# Tps7A47_Tps7A33.net
KiCad netlist of a schematic drawn in EasyEDA Pro
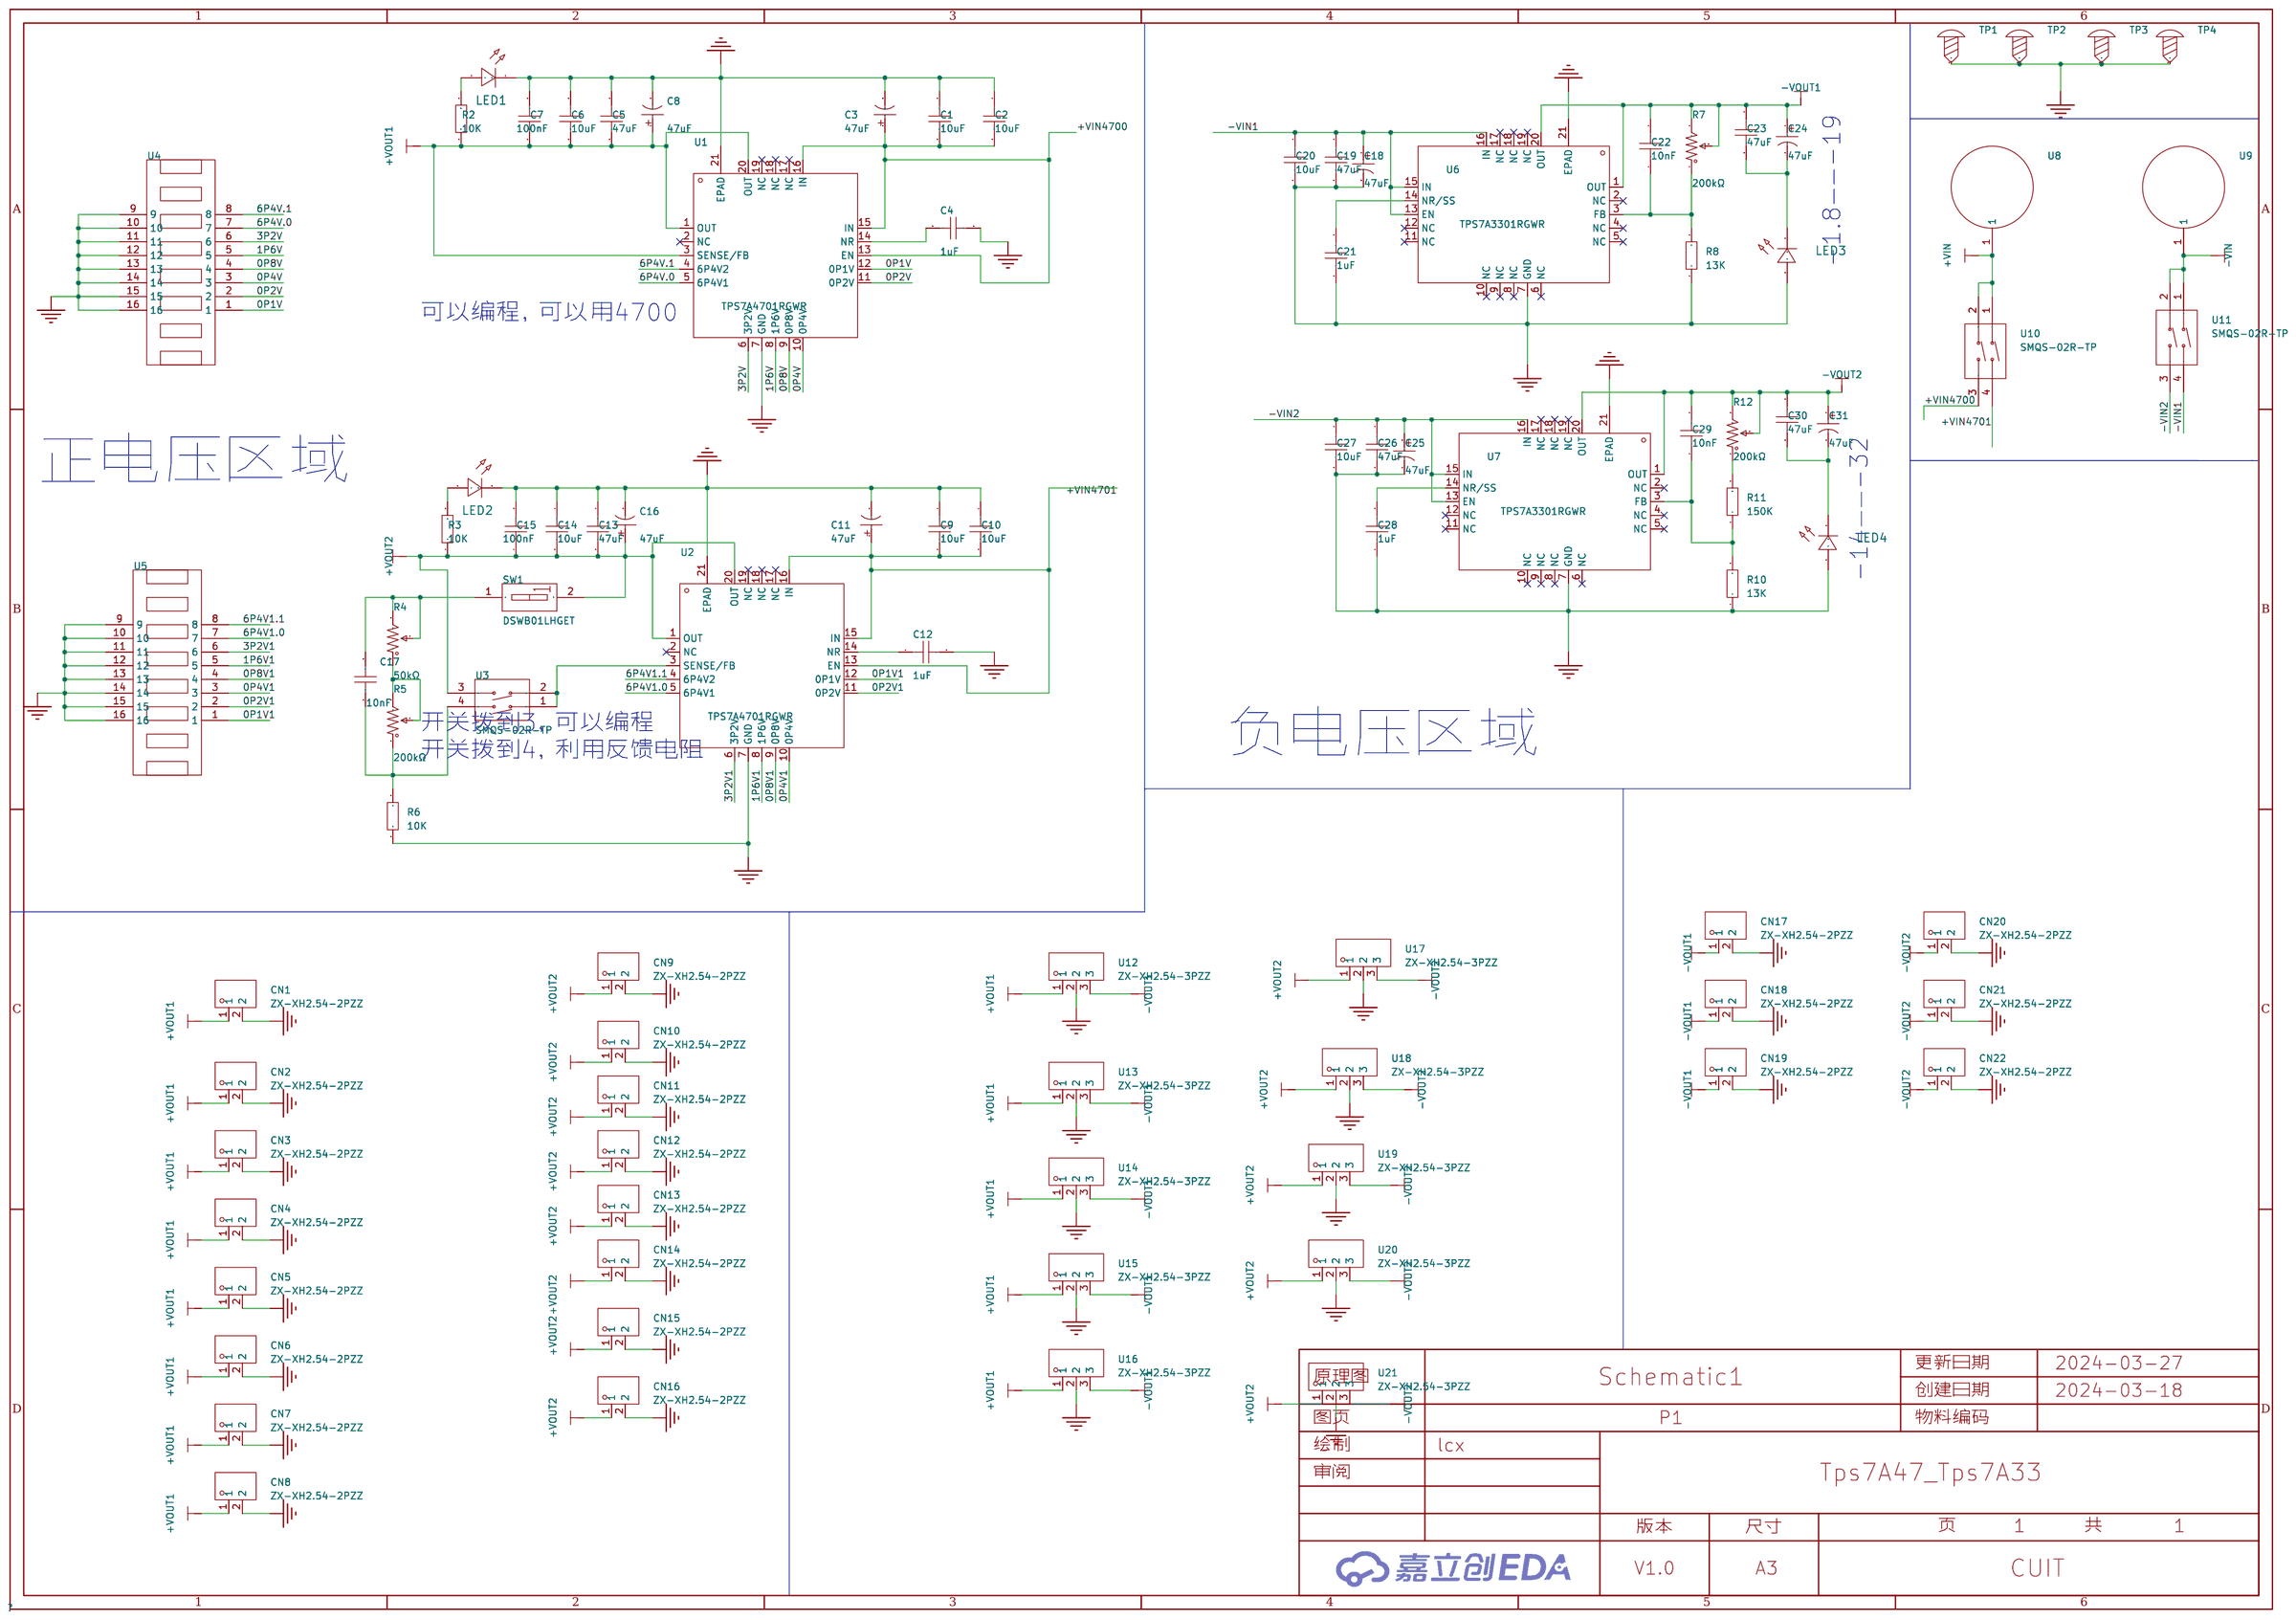
[diagram p0: schematic sheet]

(export (version "E")
  (design (tool "Eeschema 10.0.6"))
  (components
    (comp (ref "C1")
      (value "10uF")
      (footprint "easyedapro:C1206")
      (libsource (lib "easyedapro") (part "CapAcitance"))
    )
    (comp (ref "C2")
      (value "10uF")
      (footprint "easyedapro:C1206")
      (libsource (lib "easyedapro") (part "CapAcitance"))
    )
    (comp (ref "C3")
      (value "47uF")
      (footprint "easyedapro:CAP-SMD_BD6.3-L6.6-W6.6-LS7.6-FD")
      (description "容值:47uF;精度:±20%;额定电压:50V;纹波电流:66mA@120Hz;等效串联电阻:-;")
      (fields (field (name "Manufacturer Part") "RVT1H470M0607") (field (name "Manufacturer") "ROQANG(容强)"))
      (libsource (lib "easyedapro") (part "RVT1H470M0607"))
    )
    (comp (ref "C4")
      (value "1uF")
      (footprint "easyedapro:C1206")
      (libsource (lib "easyedapro") (part "CapAcitance"))
    )
    (comp (ref "C5")
      (value "47uF")
      (footprint "easyedapro:C1206")
      (libsource (lib "easyedapro") (part "CapAcitance"))
    )
    (comp (ref "C6")
      (value "10uF")
      (footprint "easyedapro:C1206")
      (libsource (lib "easyedapro") (part "CapAcitance"))
    )
    (comp (ref "C7")
      (value "100nF")
      (footprint "easyedapro:C1206")
      (libsource (lib "easyedapro") (part "CapAcitance"))
    )
    (comp (ref "C8")
      (value "47uF")
      (footprint "easyedapro:CAP-SMD_BD6.3-L6.6-W6.6-LS7.6-FD")
      (description "容值:47uF;精度:±20%;额定电压:50V;纹波电流:66mA@120Hz;等效串联电阻:-;")
      (fields (field (name "Manufacturer Part") "RVT1H470M0607") (field (name "Manufacturer") "ROQANG(容强)"))
      (libsource (lib "easyedapro") (part "RVT1H470M0607"))
    )
    (comp (ref "C9")
      (value "10uF")
      (footprint "easyedapro:C1206")
      (libsource (lib "easyedapro") (part "CapAcitance"))
    )
    (comp (ref "C10")
      (value "10uF")
      (footprint "easyedapro:C1206")
      (libsource (lib "easyedapro") (part "CapAcitance"))
    )
    (comp (ref "C11")
      (value "47uF")
      (footprint "easyedapro:CAP-SMD_BD6.3-L6.6-W6.6-LS7.6-FD")
      (description "容值:47uF;精度:±20%;额定电压:50V;纹波电流:66mA@120Hz;等效串联电阻:-;")
      (fields (field (name "Manufacturer Part") "RVT1H470M0607") (field (name "Manufacturer") "ROQANG(容强)"))
      (libsource (lib "easyedapro") (part "RVT1H470M0607"))
    )
    (comp (ref "C12")
      (value "1uF")
      (footprint "easyedapro:C1206")
      (libsource (lib "easyedapro") (part "CapAcitance"))
    )
    (comp (ref "C13")
      (value "47uF")
      (footprint "easyedapro:C1206")
      (libsource (lib "easyedapro") (part "CapAcitance"))
    )
    (comp (ref "C14")
      (value "10uF")
      (footprint "easyedapro:C1206")
      (libsource (lib "easyedapro") (part "CapAcitance"))
    )
    (comp (ref "C15")
      (value "100nF")
      (footprint "easyedapro:C1206")
      (libsource (lib "easyedapro") (part "CapAcitance"))
    )
    (comp (ref "C16")
      (value "47uF")
      (footprint "easyedapro:CAP-SMD_BD6.3-L6.6-W6.6-LS7.6-FD")
      (description "容值:47uF;精度:±20%;额定电压:50V;纹波电流:66mA@120Hz;等效串联电阻:-;")
      (fields (field (name "Manufacturer Part") "RVT1H470M0607") (field (name "Manufacturer") "ROQANG(容强)"))
      (libsource (lib "easyedapro") (part "RVT1H470M0607"))
    )
    (comp (ref "C17")
      (value "10nF")
      (footprint "easyedapro:C1206")
      (libsource (lib "easyedapro") (part "CapAcitance"))
    )
    (comp (ref "C18")
      (value "47uF")
      (footprint "easyedapro:CAP-SMD_BD6.3-L6.6-W6.6-LS7.6-FD")
      (description "容值:47uF;精度:±20%;额定电压:50V;纹波电流:66mA@120Hz;等效串联电阻:-;")
      (fields (field (name "Manufacturer Part") "RVT1H470M0607") (field (name "Manufacturer") "ROQANG(容强)"))
      (libsource (lib "easyedapro") (part "RVT1H470M0607"))
    )
    (comp (ref "C19")
      (value "47uF")
      (footprint "easyedapro:C1206")
      (libsource (lib "easyedapro") (part "CapAcitance"))
    )
    (comp (ref "C20")
      (value "10uF")
      (footprint "easyedapro:C1206")
      (libsource (lib "easyedapro") (part "CapAcitance"))
    )
    (comp (ref "C21")
      (value "1uF")
      (footprint "easyedapro:C1206")
      (libsource (lib "easyedapro") (part "CapAcitance"))
    )
    (comp (ref "C22")
      (value "10nF")
      (footprint "easyedapro:C1206")
      (libsource (lib "easyedapro") (part "CapAcitance"))
    )
    (comp (ref "C23")
      (value "47uF")
      (footprint "easyedapro:C1206")
      (libsource (lib "easyedapro") (part "CapAcitance"))
    )
    (comp (ref "C24")
      (value "47uF")
      (footprint "easyedapro:CAP-SMD_BD6.3-L6.6-W6.6-LS7.6-FD")
      (description "容值:47uF;精度:±20%;额定电压:50V;纹波电流:66mA@120Hz;等效串联电阻:-;")
      (fields (field (name "Manufacturer Part") "RVT1H470M0607") (field (name "Manufacturer") "ROQANG(容强)"))
      (libsource (lib "easyedapro") (part "RVT1H470M0607"))
    )
    (comp (ref "C25")
      (value "47uF")
      (footprint "easyedapro:CAP-SMD_BD6.3-L6.6-W6.6-LS7.6-FD")
      (description "容值:47uF;精度:±20%;额定电压:50V;纹波电流:66mA@120Hz;等效串联电阻:-;")
      (fields (field (name "Manufacturer Part") "RVT1H470M0607") (field (name "Manufacturer") "ROQANG(容强)"))
      (libsource (lib "easyedapro") (part "RVT1H470M0607"))
    )
    (comp (ref "C26")
      (value "47uF")
      (footprint "easyedapro:C1206")
      (libsource (lib "easyedapro") (part "CapAcitance"))
    )
    (comp (ref "C27")
      (value "10uF")
      (footprint "easyedapro:C1206")
      (libsource (lib "easyedapro") (part "CapAcitance"))
    )
    (comp (ref "C28")
      (value "1uF")
      (footprint "easyedapro:C1206")
      (libsource (lib "easyedapro") (part "CapAcitance"))
    )
    (comp (ref "C29")
      (value "10nF")
      (footprint "easyedapro:C1206")
      (libsource (lib "easyedapro") (part "CapAcitance"))
    )
    (comp (ref "C30")
      (value "47uF")
      (footprint "easyedapro:C1206")
      (libsource (lib "easyedapro") (part "CapAcitance"))
    )
    (comp (ref "C31")
      (value "47uF")
      (footprint "easyedapro:CAP-SMD_BD6.3-L6.6-W6.6-LS7.6-FD")
      (description "容值:47uF;精度:±20%;额定电压:50V;纹波电流:66mA@120Hz;等效串联电阻:-;")
      (fields (field (name "Manufacturer Part") "RVT1H470M0607") (field (name "Manufacturer") "ROQANG(容强)"))
      (libsource (lib "easyedapro") (part "RVT1H470M0607"))
    )
    (comp (ref "CN1")
      (value "ZX-XH2.54-2PZZ")
      (footprint "easyedapro:CONN-TH_2P-P2.50_HX25003-2A")
      (fields (field (name "Manufacturer") "Megastar(兆星)"))
      (libsource (lib "easyedapro") (part "ZX-XH2.54-2PZZ"))
    )
    (comp (ref "CN2")
      (value "ZX-XH2.54-2PZZ")
      (footprint "easyedapro:CONN-TH_2P-P2.50_HX25003-2A")
      (fields (field (name "Manufacturer") "Megastar(兆星)"))
      (libsource (lib "easyedapro") (part "ZX-XH2.54-2PZZ"))
    )
    (comp (ref "CN3")
      (value "ZX-XH2.54-2PZZ")
      (footprint "easyedapro:CONN-TH_2P-P2.50_HX25003-2A")
      (fields (field (name "Manufacturer") "Megastar(兆星)"))
      (libsource (lib "easyedapro") (part "ZX-XH2.54-2PZZ"))
    )
    (comp (ref "CN4")
      (value "ZX-XH2.54-2PZZ")
      (footprint "easyedapro:CONN-TH_2P-P2.50_HX25003-2A")
      (fields (field (name "Manufacturer") "Megastar(兆星)"))
      (libsource (lib "easyedapro") (part "ZX-XH2.54-2PZZ"))
    )
    (comp (ref "CN5")
      (value "ZX-XH2.54-2PZZ")
      (footprint "easyedapro:CONN-TH_2P-P2.50_HX25003-2A")
      (fields (field (name "Manufacturer") "Megastar(兆星)"))
      (libsource (lib "easyedapro") (part "ZX-XH2.54-2PZZ"))
    )
    (comp (ref "CN6")
      (value "ZX-XH2.54-2PZZ")
      (footprint "easyedapro:CONN-TH_2P-P2.50_HX25003-2A")
      (fields (field (name "Manufacturer") "Megastar(兆星)"))
      (libsource (lib "easyedapro") (part "ZX-XH2.54-2PZZ"))
    )
    (comp (ref "CN7")
      (value "ZX-XH2.54-2PZZ")
      (footprint "easyedapro:CONN-TH_2P-P2.50_HX25003-2A")
      (fields (field (name "Manufacturer") "Megastar(兆星)"))
      (libsource (lib "easyedapro") (part "ZX-XH2.54-2PZZ"))
    )
    (comp (ref "CN8")
      (value "ZX-XH2.54-2PZZ")
      (footprint "easyedapro:CONN-TH_2P-P2.50_HX25003-2A")
      (fields (field (name "Manufacturer") "Megastar(兆星)"))
      (libsource (lib "easyedapro") (part "ZX-XH2.54-2PZZ"))
    )
    (comp (ref "CN9")
      (value "ZX-XH2.54-2PZZ")
      (footprint "easyedapro:CONN-TH_2P-P2.50_HX25003-2A")
      (fields (field (name "Manufacturer") "Megastar(兆星)"))
      (libsource (lib "easyedapro") (part "ZX-XH2.54-2PZZ"))
    )
    (comp (ref "CN10")
      (value "ZX-XH2.54-2PZZ")
      (footprint "easyedapro:CONN-TH_2P-P2.50_HX25003-2A")
      (fields (field (name "Manufacturer") "Megastar(兆星)"))
      (libsource (lib "easyedapro") (part "ZX-XH2.54-2PZZ"))
    )
    (comp (ref "CN11")
      (value "ZX-XH2.54-2PZZ")
      (footprint "easyedapro:CONN-TH_2P-P2.50_HX25003-2A")
      (fields (field (name "Manufacturer") "Megastar(兆星)"))
      (libsource (lib "easyedapro") (part "ZX-XH2.54-2PZZ"))
    )
    (comp (ref "CN12")
      (value "ZX-XH2.54-2PZZ")
      (footprint "easyedapro:CONN-TH_2P-P2.50_HX25003-2A")
      (fields (field (name "Manufacturer") "Megastar(兆星)"))
      (libsource (lib "easyedapro") (part "ZX-XH2.54-2PZZ"))
    )
    (comp (ref "CN13")
      (value "ZX-XH2.54-2PZZ")
      (footprint "easyedapro:CONN-TH_2P-P2.50_HX25003-2A")
      (fields (field (name "Manufacturer") "Megastar(兆星)"))
      (libsource (lib "easyedapro") (part "ZX-XH2.54-2PZZ"))
    )
    (comp (ref "CN14")
      (value "ZX-XH2.54-2PZZ")
      (footprint "easyedapro:CONN-TH_2P-P2.50_HX25003-2A")
      (fields (field (name "Manufacturer") "Megastar(兆星)"))
      (libsource (lib "easyedapro") (part "ZX-XH2.54-2PZZ"))
    )
    (comp (ref "CN15")
      (value "ZX-XH2.54-2PZZ")
      (footprint "easyedapro:CONN-TH_2P-P2.50_HX25003-2A")
      (fields (field (name "Manufacturer") "Megastar(兆星)"))
      (libsource (lib "easyedapro") (part "ZX-XH2.54-2PZZ"))
    )
    (comp (ref "CN16")
      (value "ZX-XH2.54-2PZZ")
      (footprint "easyedapro:CONN-TH_2P-P2.50_HX25003-2A")
      (fields (field (name "Manufacturer") "Megastar(兆星)"))
      (libsource (lib "easyedapro") (part "ZX-XH2.54-2PZZ"))
    )
    (comp (ref "CN17")
      (value "ZX-XH2.54-2PZZ")
      (footprint "easyedapro:CONN-TH_2P-P2.50_HX25003-2A")
      (fields (field (name "Manufacturer") "Megastar(兆星)"))
      (libsource (lib "easyedapro") (part "ZX-XH2.54-2PZZ"))
    )
    (comp (ref "CN18")
      (value "ZX-XH2.54-2PZZ")
      (footprint "easyedapro:CONN-TH_2P-P2.50_HX25003-2A")
      (fields (field (name "Manufacturer") "Megastar(兆星)"))
      (libsource (lib "easyedapro") (part "ZX-XH2.54-2PZZ"))
    )
    (comp (ref "CN19")
      (value "ZX-XH2.54-2PZZ")
      (footprint "easyedapro:CONN-TH_2P-P2.50_HX25003-2A")
      (fields (field (name "Manufacturer") "Megastar(兆星)"))
      (libsource (lib "easyedapro") (part "ZX-XH2.54-2PZZ"))
    )
    (comp (ref "CN20")
      (value "ZX-XH2.54-2PZZ")
      (footprint "easyedapro:CONN-TH_2P-P2.50_HX25003-2A")
      (fields (field (name "Manufacturer") "Megastar(兆星)"))
      (libsource (lib "easyedapro") (part "ZX-XH2.54-2PZZ"))
    )
    (comp (ref "CN21")
      (value "ZX-XH2.54-2PZZ")
      (footprint "easyedapro:CONN-TH_2P-P2.50_HX25003-2A")
      (fields (field (name "Manufacturer") "Megastar(兆星)"))
      (libsource (lib "easyedapro") (part "ZX-XH2.54-2PZZ"))
    )
    (comp (ref "CN22")
      (value "ZX-XH2.54-2PZZ")
      (footprint "easyedapro:CONN-TH_2P-P2.50_HX25003-2A")
      (fields (field (name "Manufacturer") "Megastar(兆星)"))
      (libsource (lib "easyedapro") (part "ZX-XH2.54-2PZZ"))
    )
    (comp (ref "LED1")
      (value "~")
      (footprint "easyedapro:LED_0805")
      (libsource (lib "easyedapro") (part "LED_R"))
    )
    (comp (ref "LED2")
      (value "~")
      (footprint "easyedapro:LED_0805")
      (libsource (lib "easyedapro") (part "LED_R"))
    )
    (comp (ref "LED3")
      (value "~")
      (footprint "easyedapro:LED_0805")
      (libsource (lib "easyedapro") (part "LED_R"))
    )
    (comp (ref "LED4")
      (value "~")
      (footprint "easyedapro:LED_0805")
      (libsource (lib "easyedapro") (part "LED_R"))
    )
    (comp (ref "R2") (value "10K") (footprint "easyedapro:R0805") (libsource (lib "easyedapro") (part "电阻")))
    (comp (ref "R3") (value "10K") (footprint "easyedapro:R0805") (libsource (lib "easyedapro") (part "电阻")))
    (comp (ref "R4")
      (value "50kΩ")
      (footprint "easyedapro:RES-ADJ-TH_3P-L10.0-W10.0-P2.50-L")
      (description "阻值:10kΩ;精度:±10%;")
      (fields (field (name "Manufacturer Part") "3296W-1-103") (field (name "Manufacturer") "BOCHEN(博晨)"))
      (libsource (lib "easyedapro") (part "3296W-1-103"))
    )
    (comp (ref "R5")
      (value "200kΩ")
      (footprint "easyedapro:RES-ADJ-TH_3P-L10.0-W10.0-P2.50-L")
      (description "阻值:10kΩ;精度:±10%;")
      (fields (field (name "Manufacturer Part") "3296W-1-103") (field (name "Manufacturer") "BOCHEN(博晨)"))
      (libsource (lib "easyedapro") (part "3296W-1-103"))
    )
    (comp (ref "R6") (value "10K") (footprint "easyedapro:R0805") (libsource (lib "easyedapro") (part "电阻")))
    (comp (ref "R7")
      (value "200kΩ")
      (footprint "easyedapro:RES-ADJ-TH_3P-L10.0-W10.0-P2.50-L")
      (description "阻值:10kΩ;精度:±10%;")
      (fields (field (name "Manufacturer Part") "3296W-1-103") (field (name "Manufacturer") "BOCHEN(博晨)"))
      (libsource (lib "easyedapro") (part "3296W-1-103"))
    )
    (comp (ref "R8") (value "13K") (footprint "easyedapro:R0805") (libsource (lib "easyedapro") (part "电阻")))
    (comp (ref "R10") (value "13K") (footprint "easyedapro:R0805") (libsource (lib "easyedapro") (part "电阻")))
    (comp (ref "R11")
      (value "150K")
      (footprint "easyedapro:R0805")
      (libsource (lib "easyedapro") (part "电阻"))
    )
    (comp (ref "R12")
      (value "200kΩ")
      (footprint "easyedapro:RES-ADJ-TH_3P-L10.0-W10.0-P2.50-L")
      (description "阻值:10kΩ;精度:±10%;")
      (fields (field (name "Manufacturer Part") "3296W-1-103") (field (name "Manufacturer") "BOCHEN(博晨)"))
      (libsource (lib "easyedapro") (part "3296W-1-103"))
    )
    (comp (ref "SW1")
      (value "DSWB01LHGET")
      (footprint "easyedapro:SW-TH_DSWB01LHGET")
      (description "类型:平拨,凸起式;电路结构:单刀单掷;开关位数:1位;使用寿命:-;颜色:红色;")
      (fields (field (name "Manufacturer") "YE"))
      (libsource (lib "easyedapro") (part "DSWB01LHGET"))
    )
    (comp (ref "TP1") (value "~") (footprint "easyedapro:M2螺丝") (libsource (lib "easyedapro") (part "螺丝孔")))
    (comp (ref "TP2") (value "~") (footprint "easyedapro:M2螺丝") (libsource (lib "easyedapro") (part "螺丝孔")))
    (comp (ref "TP3") (value "~") (footprint "easyedapro:M2螺丝") (libsource (lib "easyedapro") (part "螺丝孔")))
    (comp (ref "TP4") (value "~") (footprint "easyedapro:M2螺丝") (libsource (lib "easyedapro") (part "螺丝孔")))
    (comp (ref "U1")
      (value "TPS7A4701RGWR")
      (footprint "easyedapro:VQFN-20_L5.0-W5.0-P0.65-TL-EP")
      (description "输出类型:可调;最大输入电压:35V;输出电压:1.4V~34V;最大输出电流:1A;电源纹波抑制比(PSRR):78dB@(1kHz);输出极性:正极;")
      (fields (field (name "Manufacturer") "TI(德州仪器)"))
      (libsource (lib "easyedapro") (part "TPS7A4701RGWR"))
    )
    (comp (ref "U2")
      (value "TPS7A4701RGWR")
      (footprint "easyedapro:VQFN-20_L5.0-W5.0-P0.65-TL-EP")
      (description "输出类型:可调;最大输入电压:35V;输出电压:1.4V~34V;最大输出电流:1A;电源纹波抑制比(PSRR):78dB@(1kHz);输出极性:正极;")
      (fields (field (name "Manufacturer") "TI(德州仪器)"))
      (libsource (lib "easyedapro") (part "TPS7A4701RGWR"))
    )
    (comp (ref "U3")
      (value "SMQS-02R-TP")
      (footprint "easyedapro:SW-TH_4P-L9.9-W6.8-P7.62-BL")
      (description "类型:平拨,凸起式;电路结构:-;开关位数:2位;额定电流:-;额定电压:-;使用寿命:5千次;颜色:红色;")
      (fields (field (name "Manufacturer") "SM Switch"))
      (libsource (lib "easyedapro") (part "SMQS-02R-TP"))
    )
    (comp (ref "U4") (value "~") (footprint "easyedapro:DIP16") (libsource (lib "easyedapro") (part "DS8RT")))
    (comp (ref "U5") (value "~") (footprint "easyedapro:DIP16") (libsource (lib "easyedapro") (part "DS8RT")))
    (comp (ref "U6")
      (value "TPS7A3301RGWR")
      (footprint "easyedapro:VQFN-20_L5.0-W5.0-P0.65-TL-EP")
      (description "输出类型:可调;最大输入电压:36V;输出电压:1.18V~33V;最大输出电流:1A;电源纹波抑制比(PSRR):72dB@(10kHz);输出极性:负极;")
      (fields (field (name "Manufacturer") "TI(德州仪器)"))
      (libsource (lib "easyedapro") (part "TPS7A3301RGWR"))
    )
    (comp (ref "U7")
      (value "TPS7A3301RGWR")
      (footprint "easyedapro:VQFN-20_L5.0-W5.0-P0.65-TL-EP")
      (description "输出类型:可调;最大输入电压:36V;输出电压:1.18V~33V;最大输出电流:1A;电源纹波抑制比(PSRR):72dB@(10kHz);输出极性:负极;")
      (fields (field (name "Manufacturer") "TI(德州仪器)"))
      (libsource (lib "easyedapro") (part "TPS7A3301RGWR"))
    )
    (comp (ref "U8")
      (value "~")
      (footprint "easyedapro:插座")
      (libsource (lib "easyedapro") (part "4mmbananaheader"))
    )
    (comp (ref "U9")
      (value "~")
      (footprint "easyedapro:插座")
      (libsource (lib "easyedapro") (part "4mmbananaheader"))
    )
    (comp (ref "U10")
      (value "SMQS-02R-TP")
      (footprint "easyedapro:SW-TH_4P-L9.9-W6.8-P7.62-BL")
      (description "类型:平拨,凸起式;电路结构:-;开关位数:2位;额定电流:-;额定电压:-;使用寿命:5千次;颜色:红色;")
      (fields (field (name "Manufacturer") "SM Switch"))
      (libsource (lib "easyedapro") (part "SMQS-02R-TP"))
    )
    (comp (ref "U11")
      (value "SMQS-02R-TP")
      (footprint "easyedapro:SW-TH_4P-L9.9-W6.8-P7.62-BL")
      (description "类型:平拨,凸起式;电路结构:-;开关位数:2位;额定电流:-;额定电压:-;使用寿命:5千次;颜色:红色;")
      (fields (field (name "Manufacturer") "SM Switch"))
      (libsource (lib "easyedapro") (part "SMQS-02R-TP"))
    )
    (comp (ref "U12")
      (value "ZX-XH2.54-3PZZ")
      (footprint "easyedapro:CONN-TH_3P-P2.54_2501S-3P")
      (fields (field (name "Manufacturer") "Megastar(兆星)"))
      (libsource (lib "easyedapro") (part "ZX-XH2.54-3PZZ"))
    )
    (comp (ref "U13")
      (value "ZX-XH2.54-3PZZ")
      (footprint "easyedapro:CONN-TH_3P-P2.54_2501S-3P")
      (fields (field (name "Manufacturer") "Megastar(兆星)"))
      (libsource (lib "easyedapro") (part "ZX-XH2.54-3PZZ"))
    )
    (comp (ref "U14")
      (value "ZX-XH2.54-3PZZ")
      (footprint "easyedapro:CONN-TH_3P-P2.54_2501S-3P")
      (fields (field (name "Manufacturer") "Megastar(兆星)"))
      (libsource (lib "easyedapro") (part "ZX-XH2.54-3PZZ"))
    )
    (comp (ref "U15")
      (value "ZX-XH2.54-3PZZ")
      (footprint "easyedapro:CONN-TH_3P-P2.54_2501S-3P")
      (fields (field (name "Manufacturer") "Megastar(兆星)"))
      (libsource (lib "easyedapro") (part "ZX-XH2.54-3PZZ"))
    )
    (comp (ref "U16")
      (value "ZX-XH2.54-3PZZ")
      (footprint "easyedapro:CONN-TH_3P-P2.54_2501S-3P")
      (fields (field (name "Manufacturer") "Megastar(兆星)"))
      (libsource (lib "easyedapro") (part "ZX-XH2.54-3PZZ"))
    )
    (comp (ref "U17")
      (value "ZX-XH2.54-3PZZ")
      (footprint "easyedapro:CONN-TH_3P-P2.54_2501S-3P")
      (fields (field (name "Manufacturer") "Megastar(兆星)"))
      (libsource (lib "easyedapro") (part "ZX-XH2.54-3PZZ"))
    )
    (comp (ref "U18")
      (value "ZX-XH2.54-3PZZ")
      (footprint "easyedapro:CONN-TH_3P-P2.54_2501S-3P")
      (fields (field (name "Manufacturer") "Megastar(兆星)"))
      (libsource (lib "easyedapro") (part "ZX-XH2.54-3PZZ"))
    )
    (comp (ref "U19")
      (value "ZX-XH2.54-3PZZ")
      (footprint "easyedapro:CONN-TH_3P-P2.54_2501S-3P")
      (fields (field (name "Manufacturer") "Megastar(兆星)"))
      (libsource (lib "easyedapro") (part "ZX-XH2.54-3PZZ"))
    )
    (comp (ref "U20")
      (value "ZX-XH2.54-3PZZ")
      (footprint "easyedapro:CONN-TH_3P-P2.54_2501S-3P")
      (fields (field (name "Manufacturer") "Megastar(兆星)"))
      (libsource (lib "easyedapro") (part "ZX-XH2.54-3PZZ"))
    )
    (comp (ref "U21")
      (value "ZX-XH2.54-3PZZ")
      (footprint "easyedapro:CONN-TH_3P-P2.54_2501S-3P")
      (fields (field (name "Manufacturer") "Megastar(兆星)"))
      (libsource (lib "easyedapro") (part "ZX-XH2.54-3PZZ"))
    )
  )
  (nets
    (net (code "1") (name "+VIN") (class "Default")
      (node (ref "U10") (pin "1") (pinfunction "1_1") (pintype "unspecified"))
      (node (ref "U10") (pin "2") (pinfunction "2_2") (pintype "unspecified"))
      (node (ref "U8") (pin "1") (pinfunction "1_1") (pintype "input"))
    )
    (net (code "2") (name "+VOUT1") (class "Default")
      (node (ref "C5") (pin "2") (pinfunction "2_2") (pintype "input"))
      (node (ref "C6") (pin "2") (pinfunction "2_2") (pintype "input"))
      (node (ref "C7") (pin "1") (pinfunction "1_1") (pintype "input"))
      (node (ref "C8") (pin "1") (pinfunction "1_1") (pintype "input"))
      (node (ref "CN1") (pin "1") (pinfunction "1_1") (pintype "unspecified"))
      (node (ref "CN2") (pin "1") (pinfunction "1_1") (pintype "unspecified"))
      (node (ref "CN3") (pin "1") (pinfunction "1_1") (pintype "unspecified"))
      (node (ref "CN4") (pin "1") (pinfunction "1_1") (pintype "unspecified"))
      (node (ref "CN5") (pin "1") (pinfunction "1_1") (pintype "unspecified"))
      (node (ref "CN6") (pin "1") (pinfunction "1_1") (pintype "unspecified"))
      (node (ref "CN7") (pin "1") (pinfunction "1_1") (pintype "unspecified"))
      (node (ref "CN8") (pin "1") (pinfunction "1_1") (pintype "unspecified"))
      (node (ref "R2") (pin "1") (pinfunction "1_1") (pintype "input"))
      (node (ref "U1") (pin "1") (pinfunction "OUT_1") (pintype "unspecified"))
      (node (ref "U1") (pin "20") (pinfunction "OUT_20") (pintype "unspecified"))
      (node (ref "U1") (pin "3") (pinfunction "SENSE/FB_3") (pintype "unspecified"))
      (node (ref "U12") (pin "1") (pinfunction "1_1") (pintype "unspecified"))
      (node (ref "U13") (pin "1") (pinfunction "1_1") (pintype "unspecified"))
      (node (ref "U14") (pin "1") (pinfunction "1_1") (pintype "unspecified"))
      (node (ref "U15") (pin "1") (pinfunction "1_1") (pintype "unspecified"))
      (node (ref "U16") (pin "1") (pinfunction "1_1") (pintype "unspecified"))
    )
    (net (code "3") (name "+VOUT2") (class "Default")
      (node (ref "C13") (pin "2") (pinfunction "2_2") (pintype "input"))
      (node (ref "C14") (pin "2") (pinfunction "2_2") (pintype "input"))
      (node (ref "C15") (pin "1") (pinfunction "1_1") (pintype "input"))
      (node (ref "C16") (pin "1") (pinfunction "1_1") (pintype "input"))
      (node (ref "CN10") (pin "1") (pinfunction "1_1") (pintype "unspecified"))
      (node (ref "CN11") (pin "1") (pinfunction "1_1") (pintype "unspecified"))
      (node (ref "CN12") (pin "1") (pinfunction "1_1") (pintype "unspecified"))
      (node (ref "CN13") (pin "1") (pinfunction "1_1") (pintype "unspecified"))
      (node (ref "CN14") (pin "1") (pinfunction "1_1") (pintype "unspecified"))
      (node (ref "CN15") (pin "1") (pinfunction "1_1") (pintype "unspecified"))
      (node (ref "CN16") (pin "1") (pinfunction "1_1") (pintype "unspecified"))
      (node (ref "CN9") (pin "1") (pinfunction "1_1") (pintype "unspecified"))
      (node (ref "R3") (pin "1") (pinfunction "1_1") (pintype "input"))
      (node (ref "SW1") (pin "2") (pinfunction "2_2") (pintype "input"))
      (node (ref "U17") (pin "1") (pinfunction "1_1") (pintype "unspecified"))
      (node (ref "U18") (pin "1") (pinfunction "1_1") (pintype "unspecified"))
      (node (ref "U19") (pin "1") (pinfunction "1_1") (pintype "unspecified"))
      (node (ref "U2") (pin "1") (pinfunction "OUT_1") (pintype "unspecified"))
      (node (ref "U2") (pin "20") (pinfunction "OUT_20") (pintype "unspecified"))
      (node (ref "U20") (pin "1") (pinfunction "1_1") (pintype "unspecified"))
      (node (ref "U21") (pin "1") (pinfunction "1_1") (pintype "unspecified"))
      (node (ref "U3") (pin "3") (pinfunction "3_3") (pintype "unspecified"))
    )
    (net (code "4") (name "-VIN") (class "Default")
      (node (ref "U11") (pin "1") (pinfunction "1_1") (pintype "unspecified"))
      (node (ref "U11") (pin "2") (pinfunction "2_2") (pintype "unspecified"))
      (node (ref "U9") (pin "1") (pinfunction "1_1") (pintype "input"))
    )
    (net (code "5") (name "-VOUT1") (class "Default")
      (node (ref "C22") (pin "2") (pinfunction "2_2") (pintype "input"))
      (node (ref "C23") (pin "1") (pinfunction "1_1") (pintype "input"))
      (node (ref "C24") (pin "1") (pinfunction "1_1") (pintype "input"))
      (node (ref "CN17") (pin "1") (pinfunction "1_1") (pintype "unspecified"))
      (node (ref "CN18") (pin "1") (pinfunction "1_1") (pintype "unspecified"))
      (node (ref "CN19") (pin "1") (pinfunction "1_1") (pintype "unspecified"))
      (node (ref "R7") (pin "2") (pinfunction "2_2") (pintype "input"))
      (node (ref "R7") (pin "3") (pinfunction "3_3") (pintype "input"))
      (node (ref "U12") (pin "3") (pinfunction "3_3") (pintype "unspecified"))
      (node (ref "U13") (pin "3") (pinfunction "3_3") (pintype "unspecified"))
      (node (ref "U14") (pin "3") (pinfunction "3_3") (pintype "unspecified"))
      (node (ref "U15") (pin "3") (pinfunction "3_3") (pintype "unspecified"))
      (node (ref "U16") (pin "3") (pinfunction "3_3") (pintype "unspecified"))
      (node (ref "U6") (pin "1") (pinfunction "OUT_1") (pintype "unspecified"))
      (node (ref "U6") (pin "20") (pinfunction "OUT_20") (pintype "unspecified"))
    )
    (net (code "6") (name "-VOUT2") (class "Default")
      (node (ref "C29") (pin "2") (pinfunction "2_2") (pintype "input"))
      (node (ref "C30") (pin "1") (pinfunction "1_1") (pintype "input"))
      (node (ref "C31") (pin "1") (pinfunction "1_1") (pintype "input"))
      (node (ref "CN20") (pin "1") (pinfunction "1_1") (pintype "unspecified"))
      (node (ref "CN21") (pin "1") (pinfunction "1_1") (pintype "unspecified"))
      (node (ref "CN22") (pin "1") (pinfunction "1_1") (pintype "unspecified"))
      (node (ref "R12") (pin "2") (pinfunction "2_2") (pintype "input"))
      (node (ref "R12") (pin "3") (pinfunction "3_3") (pintype "input"))
      (node (ref "U17") (pin "3") (pinfunction "3_3") (pintype "unspecified"))
      (node (ref "U18") (pin "3") (pinfunction "3_3") (pintype "unspecified"))
      (node (ref "U19") (pin "3") (pinfunction "3_3") (pintype "unspecified"))
      (node (ref "U20") (pin "3") (pinfunction "3_3") (pintype "unspecified"))
      (node (ref "U21") (pin "3") (pinfunction "3_3") (pintype "unspecified"))
      (node (ref "U7") (pin "1") (pinfunction "OUT_1") (pintype "unspecified"))
      (node (ref "U7") (pin "20") (pinfunction "OUT_20") (pintype "unspecified"))
    )
    (net (code "7") (name "/+VIN4700") (class "Default")
      (node (ref "C1") (pin "2") (pinfunction "2_2") (pintype "input"))
      (node (ref "C2") (pin "2") (pinfunction "2_2") (pintype "input"))
      (node (ref "C3") (pin "1") (pinfunction "1_1") (pintype "input"))
      (node (ref "U1") (pin "13") (pinfunction "EN_13") (pintype "unspecified"))
      (node (ref "U1") (pin "15") (pinfunction "IN_15") (pintype "unspecified"))
      (node (ref "U1") (pin "16") (pinfunction "IN_16") (pintype "unspecified"))
      (node (ref "U10") (pin "3") (pinfunction "3_3") (pintype "unspecified"))
    )
    (net (code "8") (name "/+VIN4701") (class "Default")
      (node (ref "C10") (pin "2") (pinfunction "2_2") (pintype "input"))
      (node (ref "C11") (pin "1") (pinfunction "1_1") (pintype "input"))
      (node (ref "C9") (pin "2") (pinfunction "2_2") (pintype "input"))
      (node (ref "U10") (pin "4") (pinfunction "4_4") (pintype "unspecified"))
      (node (ref "U2") (pin "13") (pinfunction "EN_13") (pintype "unspecified"))
      (node (ref "U2") (pin "15") (pinfunction "IN_15") (pintype "unspecified"))
      (node (ref "U2") (pin "16") (pinfunction "IN_16") (pintype "unspecified"))
    )
    (net (code "9") (name "/-VIN1") (class "Default")
      (node (ref "C18") (pin "1") (pinfunction "1_1") (pintype "input"))
      (node (ref "C19") (pin "1") (pinfunction "1_1") (pintype "input"))
      (node (ref "C20") (pin "1") (pinfunction "1_1") (pintype "input"))
      (node (ref "U11") (pin "4") (pinfunction "4_4") (pintype "unspecified"))
      (node (ref "U6") (pin "13") (pinfunction "EN_13") (pintype "unspecified"))
      (node (ref "U6") (pin "15") (pinfunction "IN_15") (pintype "unspecified"))
      (node (ref "U6") (pin "16") (pinfunction "IN_16") (pintype "unspecified"))
    )
    (net (code "10") (name "/-VIN2") (class "Default")
      (node (ref "C25") (pin "1") (pinfunction "1_1") (pintype "input"))
      (node (ref "C26") (pin "1") (pinfunction "1_1") (pintype "input"))
      (node (ref "C27") (pin "1") (pinfunction "1_1") (pintype "input"))
      (node (ref "U11") (pin "3") (pinfunction "3_3") (pintype "unspecified"))
      (node (ref "U7") (pin "13") (pinfunction "EN_13") (pintype "unspecified"))
      (node (ref "U7") (pin "15") (pinfunction "IN_15") (pintype "unspecified"))
      (node (ref "U7") (pin "16") (pinfunction "IN_16") (pintype "unspecified"))
    )
    (net (code "11") (name "/0P1V") (class "Default")
      (node (ref "U1") (pin "12") (pinfunction "0P1V_12") (pintype "unspecified"))
      (node (ref "U4") (pin "1") (pinfunction "1_1") (pintype "input"))
    )
    (net (code "12") (name "/0P1V1") (class "Default")
      (node (ref "U2") (pin "12") (pinfunction "0P1V_12") (pintype "unspecified"))
      (node (ref "U5") (pin "1") (pinfunction "1_1") (pintype "input"))
    )
    (net (code "13") (name "/0P2V") (class "Default")
      (node (ref "U1") (pin "11") (pinfunction "0P2V_11") (pintype "unspecified"))
      (node (ref "U4") (pin "2") (pinfunction "2_2") (pintype "input"))
    )
    (net (code "14") (name "/0P2V1") (class "Default")
      (node (ref "U2") (pin "11") (pinfunction "0P2V_11") (pintype "unspecified"))
      (node (ref "U5") (pin "2") (pinfunction "2_2") (pintype "input"))
    )
    (net (code "15") (name "/0P4V") (class "Default")
      (node (ref "U1") (pin "10") (pinfunction "0P4V_10") (pintype "unspecified"))
      (node (ref "U4") (pin "3") (pinfunction "3_3") (pintype "input"))
    )
    (net (code "16") (name "/0P4V1") (class "Default")
      (node (ref "U2") (pin "10") (pinfunction "0P4V_10") (pintype "unspecified"))
      (node (ref "U5") (pin "3") (pinfunction "3_3") (pintype "input"))
    )
    (net (code "17") (name "/0P8V") (class "Default")
      (node (ref "U1") (pin "9") (pinfunction "0P8V_9") (pintype "unspecified"))
      (node (ref "U4") (pin "4") (pinfunction "4_4") (pintype "input"))
    )
    (net (code "18") (name "/0P8V1") (class "Default")
      (node (ref "U2") (pin "9") (pinfunction "0P8V_9") (pintype "unspecified"))
      (node (ref "U5") (pin "4") (pinfunction "4_4") (pintype "input"))
    )
    (net (code "19") (name "/1P6V") (class "Default")
      (node (ref "U1") (pin "8") (pinfunction "1P6V_8") (pintype "unspecified"))
      (node (ref "U4") (pin "5") (pinfunction "5_5") (pintype "input"))
    )
    (net (code "20") (name "/1P6V1") (class "Default")
      (node (ref "U2") (pin "8") (pinfunction "1P6V_8") (pintype "unspecified"))
      (node (ref "U5") (pin "5") (pinfunction "5_5") (pintype "input"))
    )
    (net (code "21") (name "/3P2V") (class "Default")
      (node (ref "U1") (pin "6") (pinfunction "3P2V_6") (pintype "unspecified"))
      (node (ref "U4") (pin "6") (pinfunction "6_6") (pintype "input"))
    )
    (net (code "22") (name "/3P2V1") (class "Default")
      (node (ref "U2") (pin "6") (pinfunction "3P2V_6") (pintype "unspecified"))
      (node (ref "U5") (pin "6") (pinfunction "6_6") (pintype "input"))
    )
    (net (code "23") (name "/6P4V.0") (class "Default")
      (node (ref "U1") (pin "5") (pinfunction "6P4V1_5") (pintype "unspecified"))
      (node (ref "U4") (pin "7") (pinfunction "7_7") (pintype "input"))
    )
    (net (code "24") (name "/6P4V.1") (class "Default")
      (node (ref "U1") (pin "4") (pinfunction "6P4V2_4") (pintype "unspecified"))
      (node (ref "U4") (pin "8") (pinfunction "8_8") (pintype "input"))
    )
    (net (code "25") (name "/6P4V1.0") (class "Default")
      (node (ref "U2") (pin "5") (pinfunction "6P4V1_5") (pintype "unspecified"))
      (node (ref "U5") (pin "7") (pinfunction "7_7") (pintype "input"))
    )
    (net (code "26") (name "/6P4V1.1") (class "Default")
      (node (ref "U2") (pin "4") (pinfunction "6P4V2_4") (pintype "unspecified"))
      (node (ref "U5") (pin "8") (pinfunction "8_8") (pintype "input"))
    )
    (net (code "27") (name "GND") (class "Default")
      (node (ref "C1") (pin "1") (pinfunction "1_1") (pintype "input"))
      (node (ref "C10") (pin "1") (pinfunction "1_1") (pintype "input"))
      (node (ref "C11") (pin "2") (pinfunction "2_2") (pintype "input"))
      (node (ref "C12") (pin "2") (pinfunction "2_2") (pintype "input"))
      (node (ref "C13") (pin "1") (pinfunction "1_1") (pintype "input"))
      (node (ref "C14") (pin "1") (pinfunction "1_1") (pintype "input"))
      (node (ref "C15") (pin "2") (pinfunction "2_2") (pintype "input"))
      (node (ref "C16") (pin "2") (pinfunction "2_2") (pintype "input"))
      (node (ref "C18") (pin "2") (pinfunction "2_2") (pintype "input"))
      (node (ref "C19") (pin "2") (pinfunction "2_2") (pintype "input"))
      (node (ref "C2") (pin "1") (pinfunction "1_1") (pintype "input"))
      (node (ref "C20") (pin "2") (pinfunction "2_2") (pintype "input"))
      (node (ref "C21") (pin "1") (pinfunction "1_1") (pintype "input"))
      (node (ref "C25") (pin "2") (pinfunction "2_2") (pintype "input"))
      (node (ref "C26") (pin "2") (pinfunction "2_2") (pintype "input"))
      (node (ref "C27") (pin "2") (pinfunction "2_2") (pintype "input"))
      (node (ref "C28") (pin "1") (pinfunction "1_1") (pintype "input"))
      (node (ref "C3") (pin "2") (pinfunction "2_2") (pintype "input"))
      (node (ref "C4") (pin "2") (pinfunction "2_2") (pintype "input"))
      (node (ref "C5") (pin "1") (pinfunction "1_1") (pintype "input"))
      (node (ref "C6") (pin "1") (pinfunction "1_1") (pintype "input"))
      (node (ref "C7") (pin "2") (pinfunction "2_2") (pintype "input"))
      (node (ref "C8") (pin "2") (pinfunction "2_2") (pintype "input"))
      (node (ref "C9") (pin "1") (pinfunction "1_1") (pintype "input"))
      (node (ref "CN1") (pin "2") (pinfunction "2_2") (pintype "unspecified"))
      (node (ref "CN10") (pin "2") (pinfunction "2_2") (pintype "unspecified"))
      (node (ref "CN11") (pin "2") (pinfunction "2_2") (pintype "unspecified"))
      (node (ref "CN12") (pin "2") (pinfunction "2_2") (pintype "unspecified"))
      (node (ref "CN13") (pin "2") (pinfunction "2_2") (pintype "unspecified"))
      (node (ref "CN14") (pin "2") (pinfunction "2_2") (pintype "unspecified"))
      (node (ref "CN15") (pin "2") (pinfunction "2_2") (pintype "unspecified"))
      (node (ref "CN16") (pin "2") (pinfunction "2_2") (pintype "unspecified"))
      (node (ref "CN17") (pin "2") (pinfunction "2_2") (pintype "unspecified"))
      (node (ref "CN18") (pin "2") (pinfunction "2_2") (pintype "unspecified"))
      (node (ref "CN19") (pin "2") (pinfunction "2_2") (pintype "unspecified"))
      (node (ref "CN2") (pin "2") (pinfunction "2_2") (pintype "unspecified"))
      (node (ref "CN20") (pin "2") (pinfunction "2_2") (pintype "unspecified"))
      (node (ref "CN21") (pin "2") (pinfunction "2_2") (pintype "unspecified"))
      (node (ref "CN22") (pin "2") (pinfunction "2_2") (pintype "unspecified"))
      (node (ref "CN3") (pin "2") (pinfunction "2_2") (pintype "unspecified"))
      (node (ref "CN4") (pin "2") (pinfunction "2_2") (pintype "unspecified"))
      (node (ref "CN5") (pin "2") (pinfunction "2_2") (pintype "unspecified"))
      (node (ref "CN6") (pin "2") (pinfunction "2_2") (pintype "unspecified"))
      (node (ref "CN7") (pin "2") (pinfunction "2_2") (pintype "unspecified"))
      (node (ref "CN8") (pin "2") (pinfunction "2_2") (pintype "unspecified"))
      (node (ref "CN9") (pin "2") (pinfunction "2_2") (pintype "unspecified"))
      (node (ref "LED1") (pin "1") (pinfunction "C_1") (pintype "input"))
      (node (ref "LED2") (pin "1") (pinfunction "C_1") (pintype "input"))
      (node (ref "LED3") (pin "2") (pinfunction "A_2") (pintype "input"))
      (node (ref "LED4") (pin "2") (pinfunction "A_2") (pintype "input"))
      (node (ref "R10") (pin "1") (pinfunction "1_1") (pintype "input"))
      (node (ref "R6") (pin "1") (pinfunction "1_1") (pintype "input"))
      (node (ref "R8") (pin "1") (pinfunction "1_1") (pintype "input"))
      (node (ref "TP1") (pin "1") (pinfunction "1_1") (pintype "input"))
      (node (ref "TP2") (pin "1") (pinfunction "1_1") (pintype "input"))
      (node (ref "TP3") (pin "1") (pinfunction "1_1") (pintype "input"))
      (node (ref "TP4") (pin "1") (pinfunction "1_1") (pintype "input"))
      (node (ref "U1") (pin "21") (pinfunction "EPAD_21") (pintype "unspecified"))
      (node (ref "U1") (pin "7") (pinfunction "GND_7") (pintype "unspecified"))
      (node (ref "U12") (pin "2") (pinfunction "2_2") (pintype "unspecified"))
      (node (ref "U13") (pin "2") (pinfunction "2_2") (pintype "unspecified"))
      (node (ref "U14") (pin "2") (pinfunction "2_2") (pintype "unspecified"))
      (node (ref "U15") (pin "2") (pinfunction "2_2") (pintype "unspecified"))
      (node (ref "U16") (pin "2") (pinfunction "2_2") (pintype "unspecified"))
      (node (ref "U17") (pin "2") (pinfunction "2_2") (pintype "unspecified"))
      (node (ref "U18") (pin "2") (pinfunction "2_2") (pintype "unspecified"))
      (node (ref "U19") (pin "2") (pinfunction "2_2") (pintype "unspecified"))
      (node (ref "U2") (pin "21") (pinfunction "EPAD_21") (pintype "unspecified"))
      (node (ref "U2") (pin "7") (pinfunction "GND_7") (pintype "unspecified"))
      (node (ref "U20") (pin "2") (pinfunction "2_2") (pintype "unspecified"))
      (node (ref "U21") (pin "2") (pinfunction "2_2") (pintype "unspecified"))
      (node (ref "U4") (pin "10") (pinfunction "10_10") (pintype "input"))
      (node (ref "U4") (pin "11") (pinfunction "11_11") (pintype "input"))
      (node (ref "U4") (pin "12") (pinfunction "12_12") (pintype "input"))
      (node (ref "U4") (pin "13") (pinfunction "13_13") (pintype "input"))
      (node (ref "U4") (pin "14") (pinfunction "14_14") (pintype "input"))
      (node (ref "U4") (pin "15") (pinfunction "15_15") (pintype "input"))
      (node (ref "U4") (pin "16") (pinfunction "16_16") (pintype "input"))
      (node (ref "U4") (pin "9") (pinfunction "9_9") (pintype "input"))
      (node (ref "U5") (pin "10") (pinfunction "10_10") (pintype "input"))
      (node (ref "U5") (pin "11") (pinfunction "11_11") (pintype "input"))
      (node (ref "U5") (pin "12") (pinfunction "12_12") (pintype "input"))
      (node (ref "U5") (pin "13") (pinfunction "13_13") (pintype "input"))
      (node (ref "U5") (pin "14") (pinfunction "14_14") (pintype "input"))
      (node (ref "U5") (pin "15") (pinfunction "15_15") (pintype "input"))
      (node (ref "U5") (pin "16") (pinfunction "16_16") (pintype "input"))
      (node (ref "U5") (pin "9") (pinfunction "9_9") (pintype "input"))
      (node (ref "U6") (pin "21") (pinfunction "EPAD_21") (pintype "unspecified"))
      (node (ref "U6") (pin "7") (pinfunction "GND_7") (pintype "unspecified"))
      (node (ref "U7") (pin "21") (pinfunction "EPAD_21") (pintype "unspecified"))
      (node (ref "U7") (pin "7") (pinfunction "GND_7") (pintype "unspecified"))
    )
    (net (code "28") (name "Net-(C17-Pad1)") (class "Default")
      (node (ref "C17") (pin "1") (pinfunction "1_1") (pintype "input"))
      (node (ref "R5") (pin "1") (pinfunction "1_1") (pintype "input"))
      (node (ref "R6") (pin "2") (pinfunction "2_2") (pintype "input"))
      (node (ref "U3") (pin "4") (pinfunction "4_4") (pintype "unspecified"))
    )
    (net (code "29") (name "Net-(LED1-A)") (class "Default")
      (node (ref "LED1") (pin "2") (pinfunction "A_2") (pintype "input"))
      (node (ref "R2") (pin "2") (pinfunction "2_2") (pintype "input"))
    )
    (net (code "30") (name "Net-(LED2-A)") (class "Default")
      (node (ref "LED2") (pin "2") (pinfunction "A_2") (pintype "input"))
      (node (ref "R3") (pin "2") (pinfunction "2_2") (pintype "input"))
    )
    (net (code "31") (name "Net-(LED3-C)") (class "Default")
      (node (ref "C23") (pin "2") (pinfunction "2_2") (pintype "input"))
      (node (ref "C24") (pin "2") (pinfunction "2_2") (pintype "input"))
      (node (ref "LED3") (pin "1") (pinfunction "C_1") (pintype "input"))
    )
    (net (code "32") (name "Net-(LED4-C)") (class "Default")
      (node (ref "C30") (pin "2") (pinfunction "2_2") (pintype "input"))
      (node (ref "C31") (pin "2") (pinfunction "2_2") (pintype "input"))
      (node (ref "LED4") (pin "1") (pinfunction "C_1") (pintype "input"))
    )
    (net (code "33") (name "Net-(R4-Pad1)") (class "Default")
      (node (ref "R4") (pin "1") (pinfunction "1_1") (pintype "input"))
      (node (ref "R5") (pin "2") (pinfunction "2_2") (pintype "input"))
      (node (ref "R5") (pin "3") (pinfunction "3_3") (pintype "input"))
    )
    (net (code "34") (name "Net-(R11-Pad2)") (class "Default")
      (node (ref "R11") (pin "2") (pinfunction "2_2") (pintype "input"))
      (node (ref "R12") (pin "1") (pinfunction "1_1") (pintype "input"))
    )
    (net (code "35") (name "Net-(SW1-A1)") (class "Default")
      (node (ref "C17") (pin "2") (pinfunction "2_2") (pintype "input"))
      (node (ref "R4") (pin "2") (pinfunction "2_2") (pintype "input"))
      (node (ref "R4") (pin "3") (pinfunction "3_3") (pintype "input"))
      (node (ref "SW1") (pin "1") (pinfunction "A1_1") (pintype "input"))
    )
    (net (code "36") (name "Net-(U1-NR)") (class "Default")
      (node (ref "C4") (pin "1") (pinfunction "1_1") (pintype "input"))
      (node (ref "U1") (pin "14") (pinfunction "NR_14") (pintype "unspecified"))
    )
    (net (code "37") (name "Net-(U2-NR)") (class "Default")
      (node (ref "C12") (pin "1") (pinfunction "1_1") (pintype "input"))
      (node (ref "U2") (pin "14") (pinfunction "NR_14") (pintype "unspecified"))
    )
    (net (code "38") (name "Net-(U2-SENSE{slash}FB)") (class "Default")
      (node (ref "U2") (pin "3") (pinfunction "SENSE/FB_3") (pintype "unspecified"))
      (node (ref "U3") (pin "1") (pinfunction "1_1") (pintype "unspecified"))
      (node (ref "U3") (pin "2") (pinfunction "2_2") (pintype "unspecified"))
    )
    (net (code "39") (name "Net-(U6-FB)") (class "Default")
      (node (ref "C22") (pin "1") (pinfunction "1_1") (pintype "input"))
      (node (ref "R7") (pin "1") (pinfunction "1_1") (pintype "input"))
      (node (ref "R8") (pin "2") (pinfunction "2_2") (pintype "input"))
      (node (ref "U6") (pin "3") (pinfunction "FB_3") (pintype "unspecified"))
    )
    (net (code "40") (name "Net-(U6-NR{slash}SS)") (class "Default")
      (node (ref "C21") (pin "2") (pinfunction "2_2") (pintype "input"))
      (node (ref "U6") (pin "14") (pinfunction "NR/SS_14") (pintype "unspecified"))
    )
    (net (code "41") (name "Net-(U7-FB)") (class "Default")
      (node (ref "C29") (pin "1") (pinfunction "1_1") (pintype "input"))
      (node (ref "R10") (pin "2") (pinfunction "2_2") (pintype "input"))
      (node (ref "R11") (pin "1") (pinfunction "1_1") (pintype "input"))
      (node (ref "U7") (pin "3") (pinfunction "FB_3") (pintype "unspecified"))
    )
    (net (code "42") (name "Net-(U7-NR{slash}SS)") (class "Default")
      (node (ref "C28") (pin "2") (pinfunction "2_2") (pintype "input"))
      (node (ref "U7") (pin "14") (pinfunction "NR/SS_14") (pintype "unspecified"))
    )
    (net (code "43") (name "unconnected-(U1-NC-Pad2)") (class "Default")
      (node (ref "U1") (pin "2") (pinfunction "NC_2") (pintype "unspecified+no_connect"))
    )
    (net (code "44") (name "unconnected-(U1-NC-Pad17)") (class "Default")
      (node (ref "U1") (pin "17") (pinfunction "NC_17") (pintype "unspecified+no_connect"))
    )
    (net (code "45") (name "unconnected-(U1-NC-Pad18)") (class "Default")
      (node (ref "U1") (pin "18") (pinfunction "NC_18") (pintype "unspecified+no_connect"))
    )
    (net (code "46") (name "unconnected-(U1-NC-Pad19)") (class "Default")
      (node (ref "U1") (pin "19") (pinfunction "NC_19") (pintype "unspecified+no_connect"))
    )
    (net (code "47") (name "unconnected-(U2-NC-Pad2)") (class "Default")
      (node (ref "U2") (pin "2") (pinfunction "NC_2") (pintype "unspecified+no_connect"))
    )
    (net (code "48") (name "unconnected-(U2-NC-Pad17)") (class "Default")
      (node (ref "U2") (pin "17") (pinfunction "NC_17") (pintype "unspecified+no_connect"))
    )
    (net (code "49") (name "unconnected-(U2-NC-Pad18)") (class "Default")
      (node (ref "U2") (pin "18") (pinfunction "NC_18") (pintype "unspecified+no_connect"))
    )
    (net (code "50") (name "unconnected-(U2-NC-Pad19)") (class "Default")
      (node (ref "U2") (pin "19") (pinfunction "NC_19") (pintype "unspecified+no_connect"))
    )
    (net (code "51") (name "unconnected-(U6-NC-Pad2)") (class "Default")
      (node (ref "U6") (pin "2") (pinfunction "NC_2") (pintype "unspecified+no_connect"))
    )
    (net (code "52") (name "unconnected-(U6-NC-Pad4)") (class "Default")
      (node (ref "U6") (pin "4") (pinfunction "NC_4") (pintype "unspecified+no_connect"))
    )
    (net (code "53") (name "unconnected-(U6-NC-Pad5)") (class "Default")
      (node (ref "U6") (pin "5") (pinfunction "NC_5") (pintype "unspecified+no_connect"))
    )
    (net (code "54") (name "unconnected-(U6-NC-Pad6)") (class "Default")
      (node (ref "U6") (pin "6") (pinfunction "NC_6") (pintype "unspecified+no_connect"))
    )
    (net (code "55") (name "unconnected-(U6-NC-Pad8)") (class "Default")
      (node (ref "U6") (pin "8") (pinfunction "NC_8") (pintype "unspecified+no_connect"))
    )
    (net (code "56") (name "unconnected-(U6-NC-Pad9)") (class "Default")
      (node (ref "U6") (pin "9") (pinfunction "NC_9") (pintype "unspecified+no_connect"))
    )
    (net (code "57") (name "unconnected-(U6-NC-Pad10)") (class "Default")
      (node (ref "U6") (pin "10") (pinfunction "NC_10") (pintype "unspecified+no_connect"))
    )
    (net (code "58") (name "unconnected-(U6-NC-Pad11)") (class "Default")
      (node (ref "U6") (pin "11") (pinfunction "NC_11") (pintype "unspecified+no_connect"))
    )
    (net (code "59") (name "unconnected-(U6-NC-Pad12)") (class "Default")
      (node (ref "U6") (pin "12") (pinfunction "NC_12") (pintype "unspecified+no_connect"))
    )
    (net (code "60") (name "unconnected-(U6-NC-Pad17)") (class "Default")
      (node (ref "U6") (pin "17") (pinfunction "NC_17") (pintype "unspecified+no_connect"))
    )
    (net (code "61") (name "unconnected-(U6-NC-Pad18)") (class "Default")
      (node (ref "U6") (pin "18") (pinfunction "NC_18") (pintype "unspecified+no_connect"))
    )
    (net (code "62") (name "unconnected-(U6-NC-Pad19)") (class "Default")
      (node (ref "U6") (pin "19") (pinfunction "NC_19") (pintype "unspecified+no_connect"))
    )
    (net (code "63") (name "unconnected-(U7-NC-Pad2)") (class "Default")
      (node (ref "U7") (pin "2") (pinfunction "NC_2") (pintype "unspecified+no_connect"))
    )
    (net (code "64") (name "unconnected-(U7-NC-Pad4)") (class "Default")
      (node (ref "U7") (pin "4") (pinfunction "NC_4") (pintype "unspecified+no_connect"))
    )
    (net (code "65") (name "unconnected-(U7-NC-Pad5)") (class "Default")
      (node (ref "U7") (pin "5") (pinfunction "NC_5") (pintype "unspecified+no_connect"))
    )
    (net (code "66") (name "unconnected-(U7-NC-Pad6)") (class "Default")
      (node (ref "U7") (pin "6") (pinfunction "NC_6") (pintype "unspecified+no_connect"))
    )
    (net (code "67") (name "unconnected-(U7-NC-Pad8)") (class "Default")
      (node (ref "U7") (pin "8") (pinfunction "NC_8") (pintype "unspecified+no_connect"))
    )
    (net (code "68") (name "unconnected-(U7-NC-Pad9)") (class "Default")
      (node (ref "U7") (pin "9") (pinfunction "NC_9") (pintype "unspecified+no_connect"))
    )
    (net (code "69") (name "unconnected-(U7-NC-Pad10)") (class "Default")
      (node (ref "U7") (pin "10") (pinfunction "NC_10") (pintype "unspecified+no_connect"))
    )
    (net (code "70") (name "unconnected-(U7-NC-Pad11)") (class "Default")
      (node (ref "U7") (pin "11") (pinfunction "NC_11") (pintype "unspecified+no_connect"))
    )
    (net (code "71") (name "unconnected-(U7-NC-Pad12)") (class "Default")
      (node (ref "U7") (pin "12") (pinfunction "NC_12") (pintype "unspecified+no_connect"))
    )
    (net (code "72") (name "unconnected-(U7-NC-Pad17)") (class "Default")
      (node (ref "U7") (pin "17") (pinfunction "NC_17") (pintype "unspecified+no_connect"))
    )
    (net (code "73") (name "unconnected-(U7-NC-Pad18)") (class "Default")
      (node (ref "U7") (pin "18") (pinfunction "NC_18") (pintype "unspecified+no_connect"))
    )
    (net (code "74") (name "unconnected-(U7-NC-Pad19)") (class "Default")
      (node (ref "U7") (pin "19") (pinfunction "NC_19") (pintype "unspecified+no_connect"))
    )
  )
)
